# ESP32S3_Base_Schematic_v1.net
KiCad netlist of a schematic drawn in EAGLE
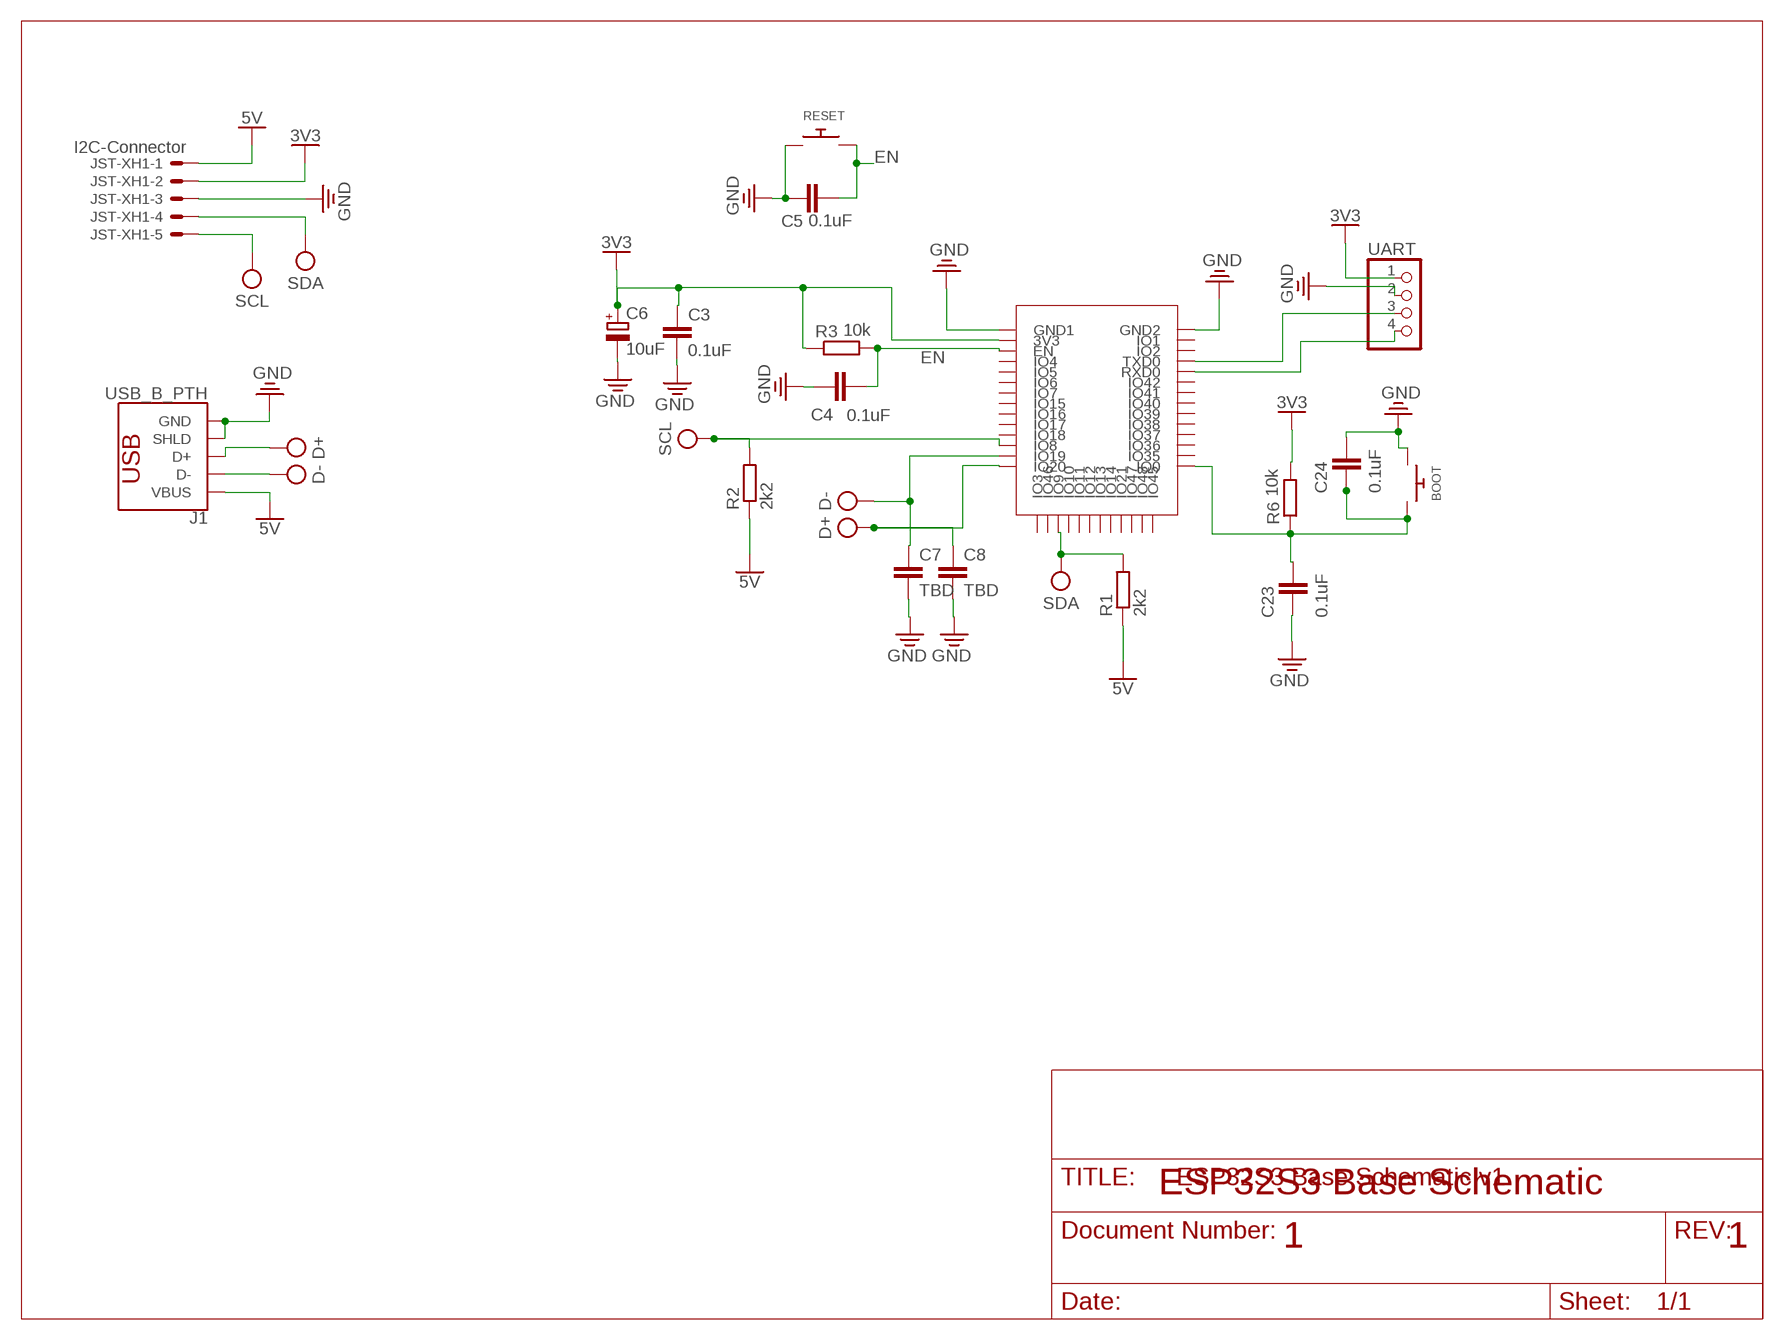
[diagram p0: schematic, sheet 1]

(export (version "E")
  (design (tool "Eeschema 10.0.6"))
  (components
    (comp (ref "BOOT")
      (value "SWITCH_PUSHBUTTONEVQ-PE")
      (footprint "eagle-import:TACT_PANA-EVQ")
      (libsource (lib "eagle-import") (part "SWITCH_PUSHBUTTONEVQ-PE"))
    )
    (comp (ref "C3")
      (value "0.1uF")
      (footprint "eagle-import:C025-030X050")
      (libsource (lib "eagle-import") (part "C-EU025-030X050"))
    )
    (comp (ref "C4")
      (value "0.1uF")
      (footprint "eagle-import:C025-030X050")
      (libsource (lib "eagle-import") (part "C-EU025-030X050"))
    )
    (comp (ref "C5")
      (value "0.1uF")
      (footprint "eagle-import:C025-030X050")
      (libsource (lib "eagle-import") (part "C-EU025-030X050"))
    )
    (comp (ref "C6")
      (value "10uF")
      (footprint "eagle-import:CAPPRD508W65D1000H1100B")
      (libsource (lib "eagle-import") (part "C-POLRADIAL-11MM-DIA_"))
    )
    (comp (ref "C7")
      (value "TBD")
      (footprint "eagle-import:C025-030X050")
      (libsource (lib "eagle-import") (part "C-EU025-030X050"))
    )
    (comp (ref "C8")
      (value "TBD")
      (footprint "eagle-import:C025-030X050")
      (libsource (lib "eagle-import") (part "C-EU025-030X050"))
    )
    (comp (ref "C23")
      (value "0.1uF")
      (footprint "eagle-import:C025-030X050")
      (libsource (lib "eagle-import") (part "C-EU025-030X050"))
    )
    (comp (ref "C24")
      (value "0.1uF")
      (footprint "eagle-import:C025-030X050")
      (libsource (lib "eagle-import") (part "C-EU025-030X050"))
    )
    (comp (ref "J1")
      (value "USB_B_PTH")
      (footprint "eagle-import:USB-B-PTH")
      (libsource (lib "eagle-import") (part "USB_B_PTH"))
    )
    (comp (ref "JST-XH1")
      (value "I2C-Connector")
      (footprint "eagle-import:JST-XH-05-PACKAGE-LONG-PAD")
      (libsource (lib "eagle-import") (part "JST-XH-05-PIN-LONG-PAD"))
    )
    (comp (ref "R1")
      (value "2k2")
      (footprint "eagle-import:0204_5")
      (libsource (lib "eagle-import") (part "R-EU_0204/5"))
    )
    (comp (ref "R2")
      (value "2k2")
      (footprint "eagle-import:0204_5")
      (libsource (lib "eagle-import") (part "R-EU_0204/5"))
    )
    (comp (ref "R3")
      (value "10k")
      (footprint "eagle-import:0204_7")
      (libsource (lib "eagle-import") (part "R-EU_0204/7"))
    )
    (comp (ref "R6")
      (value "10k")
      (footprint "eagle-import:0204_7")
      (libsource (lib "eagle-import") (part "R-EU_0204/7"))
    )
    (comp (ref "RESET")
      (value "SWITCH_PUSHBUTTONEVQ-PE")
      (footprint "eagle-import:TACT_PANA-EVQ")
      (libsource (lib "eagle-import") (part "SWITCH_PUSHBUTTONEVQ-PE"))
    )
    (comp (ref "U$2")
      (value "ESP32-S3-WROOM-1")
      (footprint "eagle-import:ESP32-S3-WROOM-1")
      (libsource (lib "eagle-import") (part "ESP32-S3-WROOM-1"))
    )
    (comp (ref "UART")
      (value "PINHD-1X4")
      (footprint "eagle-import:1X04")
      (fields (field (name "MANUFACTURER") "Generic"))
      (libsource (lib "eagle-import") (part "PINHD-1X4"))
    )
  )
  (nets
    (net (code "1") (name "/EN") (class "Default")
      (node (ref "C4") (pin "2") (pinfunction "2_2") (pintype "passive"))
      (node (ref "C5") (pin "2") (pinfunction "2_2") (pintype "passive"))
      (node (ref "R3") (pin "2") (pinfunction "2_2") (pintype "passive"))
      (node (ref "RESET") (pin "P$2") (pinfunction "P$2_P$2") (pintype "passive"))
      (node (ref "U$2") (pin "EN") (pinfunction "EN_EN") (pintype "bidirectional"))
    )
    (net (code "2") (name "3V3") (class "Default")
      (node (ref "C3") (pin "1") (pinfunction "1_1") (pintype "passive"))
      (node (ref "C6") (pin "1") (pinfunction "+_1") (pintype "passive"))
      (node (ref "JST-XH1") (pin "2") (pinfunction "S_2") (pintype "passive"))
      (node (ref "R3") (pin "1") (pinfunction "1_1") (pintype "passive"))
      (node (ref "R6") (pin "2") (pinfunction "2_2") (pintype "passive"))
      (node (ref "U$2") (pin "3V3") (pinfunction "3V3_3V3") (pintype "bidirectional"))
      (node (ref "UART") (pin "1") (pinfunction "1_1") (pintype "passive"))
    )
    (net (code "3") (name "5V") (class "Default")
      (node (ref "J1") (pin "VBUS") (pinfunction "VBUS_VBUS") (pintype "power_in"))
      (node (ref "JST-XH1") (pin "1") (pinfunction "S_1") (pintype "passive"))
      (node (ref "R1") (pin "1") (pinfunction "1_1") (pintype "passive"))
      (node (ref "R2") (pin "1") (pinfunction "1_1") (pintype "passive"))
    )
    (net (code "4") (name "D+") (class "Default")
      (node (ref "C8") (pin "1") (pinfunction "1_1") (pintype "passive"))
      (node (ref "J1") (pin "D+") (pinfunction "D+_D+") (pintype "bidirectional"))
      (node (ref "U$2") (pin "IO20") (pinfunction "IO20_IO20") (pintype "bidirectional"))
    )
    (net (code "5") (name "D-") (class "Default")
      (node (ref "C7") (pin "1") (pinfunction "1_1") (pintype "passive"))
      (node (ref "J1") (pin "D-") (pinfunction "D-_D-") (pintype "bidirectional"))
      (node (ref "U$2") (pin "IO19") (pinfunction "IO19_IO19") (pintype "bidirectional"))
    )
    (net (code "6") (name "GND") (class "Default")
      (node (ref "BOOT") (pin "P$1") (pinfunction "P$1_P$1") (pintype "passive"))
      (node (ref "C23") (pin "1") (pinfunction "1_1") (pintype "passive"))
      (node (ref "C24") (pin "2") (pinfunction "2_2") (pintype "passive"))
      (node (ref "C3") (pin "2") (pinfunction "2_2") (pintype "passive"))
      (node (ref "C4") (pin "1") (pinfunction "1_1") (pintype "passive"))
      (node (ref "C5") (pin "1") (pinfunction "1_1") (pintype "passive"))
      (node (ref "C6") (pin "2") (pinfunction "-_2") (pintype "passive"))
      (node (ref "C7") (pin "2") (pinfunction "2_2") (pintype "passive"))
      (node (ref "C8") (pin "2") (pinfunction "2_2") (pintype "passive"))
      (node (ref "J1") (pin "GND") (pinfunction "GND_GND") (pintype "power_in"))
      (node (ref "J1") (pin "SHLD1") (pinfunction "SHLD_SHLD1") (pintype "bidirectional"))
      (node (ref "J1") (pin "SHLD2") (pinfunction "SHLD_SHLD2") (pintype "bidirectional"))
      (node (ref "JST-XH1") (pin "3") (pinfunction "S_3") (pintype "passive"))
      (node (ref "RESET") (pin "P$1") (pinfunction "P$1_P$1") (pintype "passive"))
      (node (ref "U$2") (pin "GND1") (pinfunction "GND1_GND1") (pintype "bidirectional"))
      (node (ref "U$2") (pin "GND2") (pinfunction "GND2_GND2") (pintype "bidirectional"))
      (node (ref "UART") (pin "2") (pinfunction "2_2") (pintype "passive"))
    )
    (net (code "7") (name "Net-(BOOT-PadP$2)") (class "Default")
      (node (ref "BOOT") (pin "P$2") (pinfunction "P$2_P$2") (pintype "passive"))
      (node (ref "C23") (pin "2") (pinfunction "2_2") (pintype "passive"))
      (node (ref "C24") (pin "1") (pinfunction "1_1") (pintype "passive"))
      (node (ref "R6") (pin "1") (pinfunction "1_1") (pintype "passive"))
      (node (ref "U$2") (pin "IO0") (pinfunction "IO0_IO0") (pintype "bidirectional"))
    )
    (net (code "8") (name "Net-(U$2-PadRXD0)") (class "Default")
      (node (ref "U$2") (pin "RXD0") (pinfunction "RXD0_RXD0") (pintype "bidirectional"))
      (node (ref "UART") (pin "4") (pinfunction "4_4") (pintype "passive"))
    )
    (net (code "9") (name "Net-(U$2-PadTXD0)") (class "Default")
      (node (ref "U$2") (pin "TXD0") (pinfunction "TXD0_TXD0") (pintype "bidirectional"))
      (node (ref "UART") (pin "3") (pinfunction "3_3") (pintype "passive"))
    )
    (net (code "10") (name "SCL") (class "Default")
      (node (ref "JST-XH1") (pin "5") (pinfunction "S_5") (pintype "passive"))
      (node (ref "R2") (pin "2") (pinfunction "2_2") (pintype "passive"))
      (node (ref "U$2") (pin "IO8") (pinfunction "IO8_IO8") (pintype "bidirectional"))
    )
    (net (code "11") (name "SDA") (class "Default")
      (node (ref "JST-XH1") (pin "4") (pinfunction "S_4") (pintype "passive"))
      (node (ref "R1") (pin "2") (pinfunction "2_2") (pintype "passive"))
      (node (ref "U$2") (pin "IO9") (pinfunction "IO9_IO9") (pintype "bidirectional"))
    )
    (net (code "12") (name "unconnected-(U$2-PadIO1)") (class "Default")
      (node (ref "U$2") (pin "IO1") (pinfunction "IO1_IO1") (pintype "bidirectional"))
    )
    (net (code "13") (name "unconnected-(U$2-PadIO2)") (class "Default")
      (node (ref "U$2") (pin "IO2") (pinfunction "IO2_IO2") (pintype "bidirectional"))
    )
    (net (code "14") (name "unconnected-(U$2-PadIO3)") (class "Default")
      (node (ref "U$2") (pin "IO3") (pinfunction "IO3_IO3") (pintype "bidirectional"))
    )
    (net (code "15") (name "unconnected-(U$2-PadIO4)") (class "Default")
      (node (ref "U$2") (pin "IO4") (pinfunction "IO4_IO4") (pintype "bidirectional"))
    )
    (net (code "16") (name "unconnected-(U$2-PadIO5)") (class "Default")
      (node (ref "U$2") (pin "IO5") (pinfunction "IO5_IO5") (pintype "bidirectional"))
    )
    (net (code "17") (name "unconnected-(U$2-PadIO6)") (class "Default")
      (node (ref "U$2") (pin "IO6") (pinfunction "IO6_IO6") (pintype "bidirectional"))
    )
    (net (code "18") (name "unconnected-(U$2-PadIO7)") (class "Default")
      (node (ref "U$2") (pin "IO7") (pinfunction "IO7_IO7") (pintype "bidirectional"))
    )
    (net (code "19") (name "unconnected-(U$2-PadIO10)") (class "Default")
      (node (ref "U$2") (pin "IO10") (pinfunction "IO10_IO10") (pintype "bidirectional"))
    )
    (net (code "20") (name "unconnected-(U$2-PadIO11)") (class "Default")
      (node (ref "U$2") (pin "IO11") (pinfunction "IO11_IO11") (pintype "bidirectional"))
    )
    (net (code "21") (name "unconnected-(U$2-PadIO12)") (class "Default")
      (node (ref "U$2") (pin "IO12") (pinfunction "IO12_IO12") (pintype "bidirectional"))
    )
    (net (code "22") (name "unconnected-(U$2-PadIO13)") (class "Default")
      (node (ref "U$2") (pin "IO13") (pinfunction "IO13_IO13") (pintype "bidirectional"))
    )
    (net (code "23") (name "unconnected-(U$2-PadIO14)") (class "Default")
      (node (ref "U$2") (pin "IO14") (pinfunction "IO14_IO14") (pintype "bidirectional"))
    )
    (net (code "24") (name "unconnected-(U$2-PadIO15)") (class "Default")
      (node (ref "U$2") (pin "IO15") (pinfunction "IO15_IO15") (pintype "bidirectional"))
    )
    (net (code "25") (name "unconnected-(U$2-PadIO16)") (class "Default")
      (node (ref "U$2") (pin "IO16") (pinfunction "IO16_IO16") (pintype "bidirectional"))
    )
    (net (code "26") (name "unconnected-(U$2-PadIO17)") (class "Default")
      (node (ref "U$2") (pin "IO17") (pinfunction "IO17_IO17") (pintype "bidirectional"))
    )
    (net (code "27") (name "unconnected-(U$2-PadIO18)") (class "Default")
      (node (ref "U$2") (pin "IO18") (pinfunction "IO18_IO18") (pintype "bidirectional"))
    )
    (net (code "28") (name "unconnected-(U$2-PadIO21)") (class "Default")
      (node (ref "U$2") (pin "IO21") (pinfunction "IO21_IO21") (pintype "bidirectional"))
    )
    (net (code "29") (name "unconnected-(U$2-PadIO35)") (class "Default")
      (node (ref "U$2") (pin "IO35") (pinfunction "IO35_IO35") (pintype "bidirectional"))
    )
    (net (code "30") (name "unconnected-(U$2-PadIO36)") (class "Default")
      (node (ref "U$2") (pin "IO36") (pinfunction "IO36_IO36") (pintype "bidirectional"))
    )
    (net (code "31") (name "unconnected-(U$2-PadIO37)") (class "Default")
      (node (ref "U$2") (pin "IO37") (pinfunction "IO37_IO37") (pintype "bidirectional"))
    )
    (net (code "32") (name "unconnected-(U$2-PadIO38)") (class "Default")
      (node (ref "U$2") (pin "IO38") (pinfunction "IO38_IO38") (pintype "bidirectional"))
    )
    (net (code "33") (name "unconnected-(U$2-PadIO39)") (class "Default")
      (node (ref "U$2") (pin "IO39") (pinfunction "IO39_IO39") (pintype "bidirectional"))
    )
    (net (code "34") (name "unconnected-(U$2-PadIO40)") (class "Default")
      (node (ref "U$2") (pin "IO40") (pinfunction "IO40_IO40") (pintype "bidirectional"))
    )
    (net (code "35") (name "unconnected-(U$2-PadIO41)") (class "Default")
      (node (ref "U$2") (pin "IO41") (pinfunction "IO41_IO41") (pintype "bidirectional"))
    )
    (net (code "36") (name "unconnected-(U$2-PadIO42)") (class "Default")
      (node (ref "U$2") (pin "IO42") (pinfunction "IO42_IO42") (pintype "bidirectional"))
    )
    (net (code "37") (name "unconnected-(U$2-PadIO45)") (class "Default")
      (node (ref "U$2") (pin "IO45") (pinfunction "IO45_IO45") (pintype "bidirectional"))
    )
    (net (code "38") (name "unconnected-(U$2-PadIO46)") (class "Default")
      (node (ref "U$2") (pin "IO46") (pinfunction "IO46_IO46") (pintype "bidirectional"))
    )
    (net (code "39") (name "unconnected-(U$2-PadIO47)") (class "Default")
      (node (ref "U$2") (pin "IO47") (pinfunction "IO47_IO47") (pintype "bidirectional"))
    )
    (net (code "40") (name "unconnected-(U$2-PadIO48)") (class "Default")
      (node (ref "U$2") (pin "IO48") (pinfunction "IO48_IO48") (pintype "bidirectional"))
    )
  )
)
